# Motor_Driver.net
KiCad netlist of a schematic drawn in Altium Designer
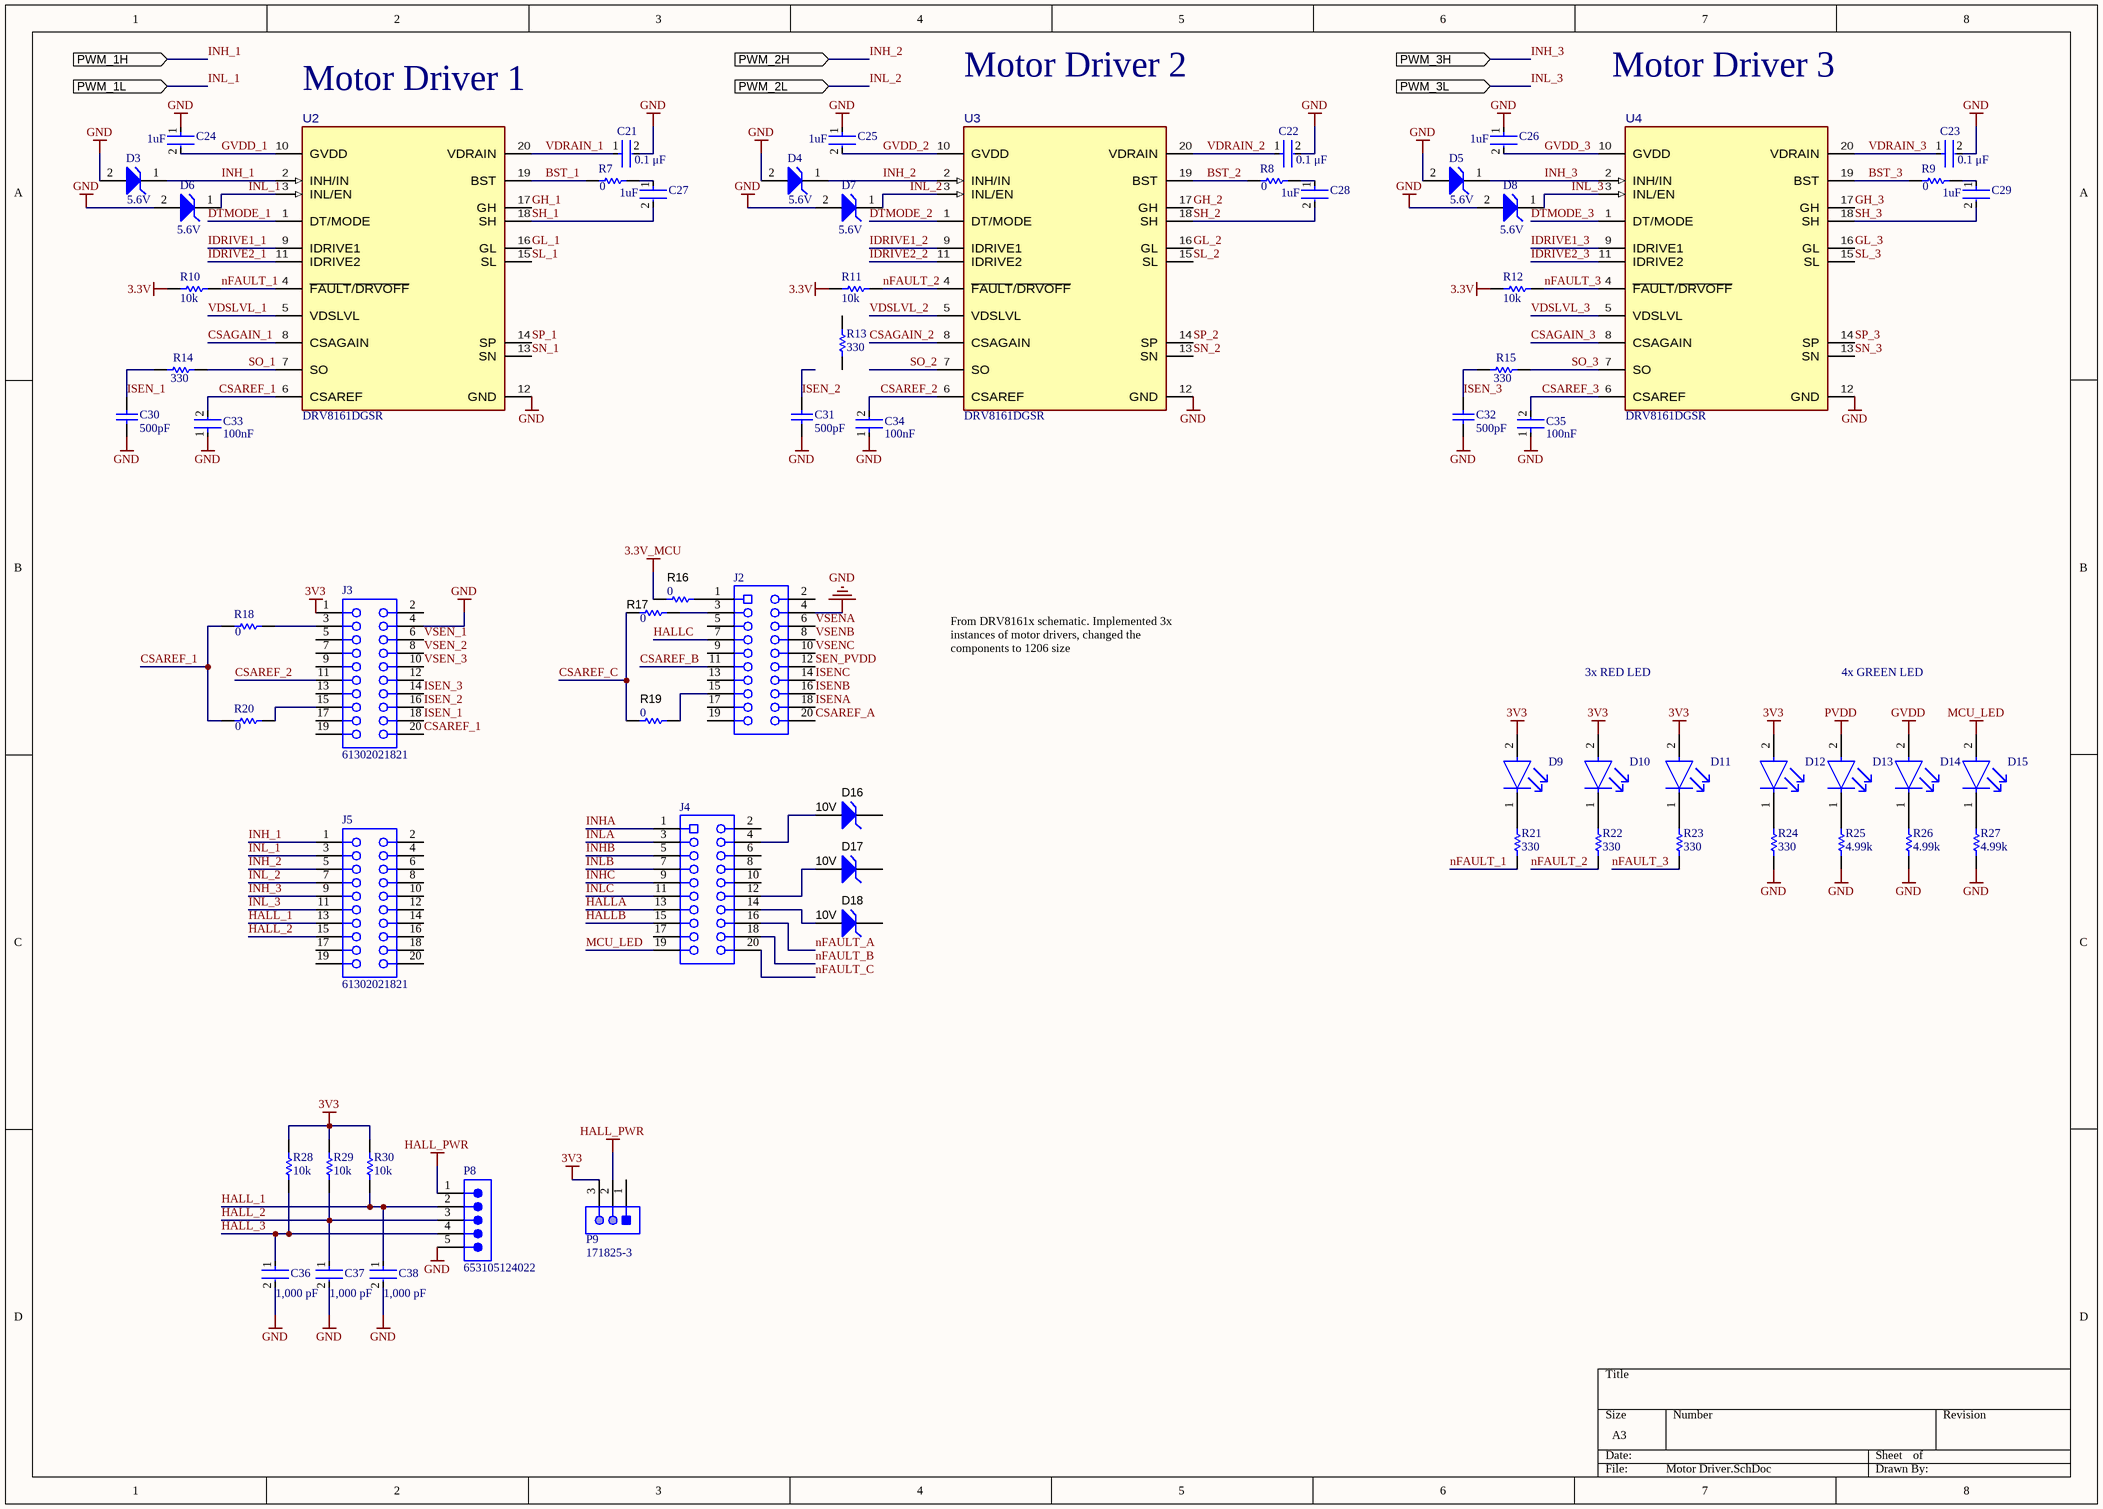
[diagram p0: Motor Driver.SchDoc]

(export (version "E")
  (design (tool "Eeschema 10.0.6"))
  (components
    (comp (ref "C21")
      (value "C1206C104K1RACTU")
      (footprint "FP-C1206C-EB-MFG")
      (description "CAP CER 0.1UF 100V X7R 1206")
      (fields
        (field (name "TOLERANCE") "0.1")
        (field (name "OCTOPART") "https://octopart.com/c1206c104k1ractu-kemet-89521")
        (field (name "CAPACITANCE") "0.1 μF")
      )
      (libsource (lib "Altium Content Vault") (part "b4654b650e69147ec39a6b967a45e02"))
    )
    (comp (ref "C22")
      (value "C1206C104K1RACTU")
      (footprint "FP-C1206C-EB-MFG")
      (description "CAP CER 0.1UF 100V X7R 1206")
      (fields
        (field (name "TOLERANCE") "0.1")
        (field (name "OCTOPART") "https://octopart.com/c1206c104k1ractu-kemet-89521")
        (field (name "CAPACITANCE") "0.1 μF")
      )
      (libsource (lib "Altium Content Vault") (part "b4654b650e69147ec39a6b967a45e02"))
    )
    (comp (ref "C23")
      (value "C1206C104K1RACTU")
      (footprint "FP-C1206C-EB-MFG")
      (description "CAP CER 0.1UF 100V X7R 1206")
      (fields
        (field (name "TOLERANCE") "0.1")
        (field (name "OCTOPART") "https://octopart.com/c1206c104k1ractu-kemet-89521")
        (field (name "CAPACITANCE") "0.1 μF")
      )
      (libsource (lib "Altium Content Vault") (part "b4654b650e69147ec39a6b967a45e02"))
    )
    (comp (ref "C24")
      (value "12063C105KAT2A")
      (footprint "FP-1206-L_3_2_0_2-W_1_6_0-IPC_A")
      (description "General Purpose Ceramic Capacitor, 1206, 1uF, 10%, X7R, 15%, 25V")
      (fields
        (field (name "CAPACITANCE") "1uF")
        (field (name "TOLERANCE") "10%")
        (field (name "VOLTAGE") "25V")
      )
      (libsource (lib "Altium Content Vault") (part "b4654b650e69147ec39a6b967a45e02"))
    )
    (comp (ref "C25")
      (value "12063C105KAT2A")
      (footprint "FP-1206-L_3_2_0_2-W_1_6_0-IPC_A")
      (description "General Purpose Ceramic Capacitor, 1206, 1uF, 10%, X7R, 15%, 25V")
      (fields
        (field (name "CAPACITANCE") "1uF")
        (field (name "TOLERANCE") "10%")
        (field (name "VOLTAGE") "25V")
      )
      (libsource (lib "Altium Content Vault") (part "b4654b650e69147ec39a6b967a45e02"))
    )
    (comp (ref "C26")
      (value "12063C105KAT2A")
      (footprint "FP-1206-L_3_2_0_2-W_1_6_0-IPC_A")
      (description "General Purpose Ceramic Capacitor, 1206, 1uF, 10%, X7R, 15%, 25V")
      (fields
        (field (name "CAPACITANCE") "1uF")
        (field (name "TOLERANCE") "10%")
        (field (name "VOLTAGE") "25V")
      )
      (libsource (lib "Altium Content Vault") (part "b4654b650e69147ec39a6b967a45e02"))
    )
    (comp (ref "C27")
      (value "12063C105KAT2A")
      (footprint "FP-1206-L_3_2_0_2-W_1_6_0-IPC_A")
      (description "General Purpose Ceramic Capacitor, 1206, 1uF, 10%, X7R, 15%, 25V")
      (fields
        (field (name "CAPACITANCE") "1uF")
        (field (name "TOLERANCE") "10%")
        (field (name "VOLTAGE") "25V")
      )
      (libsource (lib "Altium Content Vault") (part "b4654b650e69147ec39a6b967a45e02"))
    )
    (comp (ref "C28")
      (value "12063C105KAT2A")
      (footprint "FP-1206-L_3_2_0_2-W_1_6_0-IPC_A")
      (description "General Purpose Ceramic Capacitor, 1206, 1uF, 10%, X7R, 15%, 25V")
      (fields
        (field (name "CAPACITANCE") "1uF")
        (field (name "TOLERANCE") "10%")
        (field (name "VOLTAGE") "25V")
      )
      (libsource (lib "Altium Content Vault") (part "b4654b650e69147ec39a6b967a45e02"))
    )
    (comp (ref "C29")
      (value "12063C105KAT2A")
      (footprint "FP-1206-L_3_2_0_2-W_1_6_0-IPC_A")
      (description "General Purpose Ceramic Capacitor, 1206, 1uF, 10%, X7R, 15%, 25V")
      (fields
        (field (name "CAPACITANCE") "1uF")
        (field (name "TOLERANCE") "10%")
        (field (name "VOLTAGE") "25V")
      )
      (libsource (lib "Altium Content Vault") (part "b4654b650e69147ec39a6b967a45e02"))
    )
    (comp (ref "C30")
      (value "04025C501KAT2A")
      (footprint "CAPC1005X56X25NL10T15")
      (fields (field (name "MANUFACTURER") "AVX Interconnect / Elco") (field (name "PARAMETER 1") "500pF"))
      (libsource (lib "Altium Content Vault") (part "CAP"))
    )
    (comp (ref "C31")
      (value "04025C501KAT2A")
      (footprint "CAPC1005X56X25NL10T15")
      (fields (field (name "MANUFACTURER") "AVX Interconnect / Elco") (field (name "PARAMETER 1") "500pF"))
      (libsource (lib "Altium Content Vault") (part "CAP"))
    )
    (comp (ref "C32")
      (value "04025C501KAT2A")
      (footprint "CAPC1005X56X25NL10T15")
      (fields (field (name "MANUFACTURER") "AVX Interconnect / Elco") (field (name "PARAMETER 1") "500pF"))
      (libsource (lib "Altium Content Vault") (part "CAP"))
    )
    (comp (ref "C33")
      (value "12061C104KAZ2A")
      (footprint "FP-1206-L_3_2_0_2-W_1_6_0-MFG")
      (description "General Purpose Ceramic Capacitor, 1206, 100nF, 10%, X7R, 15%, 100V")
      (fields (field (name "TOLERANCE") "10%") (field (name "CAPACITANCE") "100nF"))
      (libsource (lib "Altium Content Vault") (part "b4654b650e69147ec39a6b967a45e02"))
    )
    (comp (ref "C34")
      (value "12061C104KAZ2A")
      (footprint "FP-1206-L_3_2_0_2-W_1_6_0-MFG")
      (description "General Purpose Ceramic Capacitor, 1206, 100nF, 10%, X7R, 15%, 100V")
      (fields (field (name "TOLERANCE") "10%") (field (name "CAPACITANCE") "100nF"))
      (libsource (lib "Altium Content Vault") (part "b4654b650e69147ec39a6b967a45e02"))
    )
    (comp (ref "C35")
      (value "12061C104KAZ2A")
      (footprint "FP-1206-L_3_2_0_2-W_1_6_0-MFG")
      (description "General Purpose Ceramic Capacitor, 1206, 100nF, 10%, X7R, 15%, 100V")
      (fields (field (name "TOLERANCE") "10%") (field (name "CAPACITANCE") "100nF"))
      (libsource (lib "Altium Content Vault") (part "b4654b650e69147ec39a6b967a45e02"))
    )
    (comp (ref "C36")
      (value "C1206C102J1GACTU")
      (footprint "FP-C1206C-EB-MFG")
      (fields
        (field (name "CAPACITANCE") "1,000 pF")
        (field (name "OCTOPART") "https://octopart.com/c1206c102j1gactu-kemet-99808")
        (field (name "TOLERANCE") "0.05")
        (field (name "MANUFACTURER") "KEMET")
      )
      (libsource (lib "Altium Content Vault") (part "b4654b650e69147ec39a6b967a45e02"))
    )
    (comp (ref "C37")
      (value "C1206C102J1GACTU")
      (footprint "FP-C1206C-EB-MFG")
      (fields
        (field (name "CAPACITANCE") "1,000 pF")
        (field (name "OCTOPART") "https://octopart.com/c1206c102j1gactu-kemet-99808")
        (field (name "TOLERANCE") "0.05")
        (field (name "MANUFACTURER") "KEMET")
      )
      (libsource (lib "Altium Content Vault") (part "b4654b650e69147ec39a6b967a45e02"))
    )
    (comp (ref "C38")
      (value "C1206C102J1GACTU")
      (footprint "FP-C1206C-EB-MFG")
      (fields
        (field (name "CAPACITANCE") "1,000 pF")
        (field (name "OCTOPART") "https://octopart.com/c1206c102j1gactu-kemet-99808")
        (field (name "TOLERANCE") "0.05")
        (field (name "MANUFACTURER") "KEMET")
      )
      (libsource (lib "Altium Content Vault") (part "b4654b650e69147ec39a6b967a45e02"))
    )
    (comp (ref "D3")
      (value "MMSZ5232BT1G")
      (footprint "ONSC-SOD-123-2-425-04_V")
      (description "Zener Voltage Regulator, 500 mW, 2-Pin SOD-123, Pb-Free, Tape and Reel")
      (fields (field (name "MANUFACTURER") "On Semiconductor") (field (name "VZ TYP (V)") "5.6V"))
      (libsource (lib "Altium Content Vault") (part "ONSC-K1A2-2"))
    )
    (comp (ref "D4")
      (value "MMSZ5232BT1G")
      (footprint "ONSC-SOD-123-2-425-04_V")
      (description "Zener Voltage Regulator, 500 mW, 2-Pin SOD-123, Pb-Free, Tape and Reel")
      (fields (field (name "MANUFACTURER") "On Semiconductor") (field (name "VZ TYP (V)") "5.6V"))
      (libsource (lib "Altium Content Vault") (part "ONSC-K1A2-2"))
    )
    (comp (ref "D5")
      (value "MMSZ5232BT1G")
      (footprint "ONSC-SOD-123-2-425-04_V")
      (description "Zener Voltage Regulator, 500 mW, 2-Pin SOD-123, Pb-Free, Tape and Reel")
      (fields (field (name "MANUFACTURER") "On Semiconductor") (field (name "VZ TYP (V)") "5.6V"))
      (libsource (lib "Altium Content Vault") (part "ONSC-K1A2-2"))
    )
    (comp (ref "D6")
      (value "MMSZ5232BT1G")
      (footprint "ONSC-SOD-123-2-425-04_V")
      (description "Zener Voltage Regulator, 500 mW, 2-Pin SOD-123, Pb-Free, Tape and Reel")
      (fields (field (name "MANUFACTURER") "On Semiconductor") (field (name "VZ TYP (V)") "5.6V"))
      (libsource (lib "Altium Content Vault") (part "ONSC-K1A2-2"))
    )
    (comp (ref "D7")
      (value "MMSZ5232BT1G")
      (footprint "ONSC-SOD-123-2-425-04_V")
      (description "Zener Voltage Regulator, 500 mW, 2-Pin SOD-123, Pb-Free, Tape and Reel")
      (fields (field (name "MANUFACTURER") "On Semiconductor") (field (name "VZ TYP (V)") "5.6V"))
      (libsource (lib "Altium Content Vault") (part "ONSC-K1A2-2"))
    )
    (comp (ref "D8")
      (value "MMSZ5232BT1G")
      (footprint "ONSC-SOD-123-2-425-04_V")
      (description "Zener Voltage Regulator, 500 mW, 2-Pin SOD-123, Pb-Free, Tape and Reel")
      (fields (field (name "MANUFACTURER") "On Semiconductor") (field (name "VZ TYP (V)") "5.6V"))
      (libsource (lib "Altium Content Vault") (part "ONSC-K1A2-2"))
    )
    (comp (ref "D9")
      (value "HSMS-C150")
      (footprint "FP-HSMS-C150-MFG")
      (description "LED RED DIFFUSED CHIP SMD")
      (libsource (lib "Altium Content Vault") (part "8706943c75ba83719d021d2fdc84c58"))
    )
    (comp (ref "D10")
      (value "HSMS-C150")
      (footprint "FP-HSMS-C150-MFG")
      (description "LED RED DIFFUSED CHIP SMD")
      (libsource (lib "Altium Content Vault") (part "8706943c75ba83719d021d2fdc84c58"))
    )
    (comp (ref "D11")
      (value "HSMS-C150")
      (footprint "FP-HSMS-C150-MFG")
      (description "LED RED DIFFUSED CHIP SMD")
      (libsource (lib "Altium Content Vault") (part "8706943c75ba83719d021d2fdc84c58"))
    )
    (comp (ref "D12")
      (value "LTST-C171GKT")
      (footprint "FP-LTST-C171GKT-MFG")
      (description "LED GREEN CLEAR CHIP SMD")
      (libsource (lib "Altium Content Vault") (part "8706943c75ba83719d021d2fdc84c58"))
    )
    (comp (ref "D13")
      (value "LTST-C171GKT")
      (footprint "FP-LTST-C171GKT-MFG")
      (description "LED GREEN CLEAR CHIP SMD")
      (libsource (lib "Altium Content Vault") (part "8706943c75ba83719d021d2fdc84c58"))
    )
    (comp (ref "D14")
      (value "LTST-C171GKT")
      (footprint "FP-LTST-C171GKT-MFG")
      (description "LED GREEN CLEAR CHIP SMD")
      (libsource (lib "Altium Content Vault") (part "8706943c75ba83719d021d2fdc84c58"))
    )
    (comp (ref "D15")
      (value "LTST-C171GKT")
      (footprint "FP-LTST-C171GKT-MFG")
      (description "LED GREEN CLEAR CHIP SMD")
      (libsource (lib "Altium Content Vault") (part "8706943c75ba83719d021d2fdc84c58"))
    )
    (comp (ref "D16")
      (value "10V")
      (footprint "SOD-123")
      (description "Diode, Zener, 10 V, 500 mW, SOD-123")
      (fields (field (name "MANUFACTURER") "Diodes Inc.") (field (name "PARTNUMBER") "DDZ10C-7"))
      (libsource (lib "Altium Vault - TI") (part "Zener"))
    )
    (comp (ref "D17")
      (value "10V")
      (footprint "SOD-123")
      (description "Diode, Zener, 10 V, 500 mW, SOD-123")
      (fields (field (name "MANUFACTURER") "Diodes Inc.") (field (name "PARTNUMBER") "DDZ10C-7"))
      (libsource (lib "Altium Vault - TI") (part "Zener"))
    )
    (comp (ref "D18")
      (value "10V")
      (footprint "SOD-123")
      (description "Diode, Zener, 10 V, 500 mW, SOD-123")
      (fields (field (name "MANUFACTURER") "Diodes Inc.") (field (name "PARTNUMBER") "DDZ10C-7"))
      (libsource (lib "Altium Vault - TI") (part "Zener"))
    )
    (comp (ref "J2")
      (value "SSQ-110-03-G-D")
      (footprint "Samtec_SSQ-110-03-x-D")
      (description "Receptacle, 2.54mm, 10x2, Gold, TH")
      (fields (field (name "MANUFACTURER") "Samtec") (field (name "PUBLISHER") "Texas Instruments"))
      (libsource (lib "Altium Vault - TI") (part "Receptacle_10x2"))
    )
    (comp (ref "J3")
      (value "61302021821")
      (footprint "61302021821")
      (libsource (lib "Altium Content Vault") (part "Header_Female_2R_20P"))
    )
    (comp (ref "J4")
      (value "SSQ-110-03-G-D")
      (footprint "Samtec_SSQ-110-03-x-D")
      (description "Receptacle, 2.54mm, 10x2, Gold, TH")
      (fields (field (name "MANUFACTURER") "Samtec") (field (name "PUBLISHER") "Texas Instruments"))
      (libsource (lib "Altium Vault - TI") (part "Receptacle_10x2"))
    )
    (comp (ref "J5")
      (value "61302021821")
      (footprint "61302021821")
      (libsource (lib "Altium Content Vault") (part "Header_Female_2R_20P"))
    )
    (comp (ref "P8")
      (value "653105124022")
      (footprint "653105124022")
      (libsource (lib "Altium Content Vault") (part "Header_Male_1R_05P"))
    )
    (comp (ref "P9")
      (value "171825-3")
      (footprint "TECO-171825-3_V")
      (fields (field (name "MANUFACTURER") "TE Connectivity"))
      (libsource (lib "Altium Content Vault") (part "CN-1P-M-R3"))
    )
    (comp (ref "R7")
      (value "ERJ-8GEY0R00V")
      (footprint "RESC3216X70X50NL05T20")
      (fields (field (name "MANUFACTURER") "Panasonic") (field (name "RESISTANCE") "0"))
      (libsource (lib "Altium Content Vault") (part "RES"))
    )
    (comp (ref "R8")
      (value "ERJ-8GEY0R00V")
      (footprint "RESC3216X70X50NL05T20")
      (fields (field (name "MANUFACTURER") "Panasonic") (field (name "RESISTANCE") "0"))
      (libsource (lib "Altium Content Vault") (part "RES"))
    )
    (comp (ref "R9")
      (value "ERJ-8GEY0R00V")
      (footprint "RESC3216X70X50NL05T20")
      (fields (field (name "MANUFACTURER") "Panasonic") (field (name "RESISTANCE") "0"))
      (libsource (lib "Altium Content Vault") (part "RES"))
    )
    (comp (ref "R10")
      (value "CRCW120610K0FKEAHP")
      (footprint "RESC3116X65X50NL20T20")
      (fields (field (name "MANUFACTURER") "Vishay Dale") (field (name "RESISTANCE") "10k"))
      (libsource (lib "Altium Content Vault") (part "RES"))
    )
    (comp (ref "R11")
      (value "CRCW120610K0FKEAHP")
      (footprint "RESC3116X65X50NL20T20")
      (fields (field (name "MANUFACTURER") "Vishay Dale") (field (name "RESISTANCE") "10k"))
      (libsource (lib "Altium Content Vault") (part "RES"))
    )
    (comp (ref "R12")
      (value "CRCW120610K0FKEAHP")
      (footprint "RESC3116X65X50NL20T20")
      (fields (field (name "MANUFACTURER") "Vishay Dale") (field (name "RESISTANCE") "10k"))
      (libsource (lib "Altium Content Vault") (part "RES"))
    )
    (comp (ref "R13")
      (value "ERJ-8GEYJ331V")
      (footprint "RESC3216X70X50NL05T20")
      (fields (field (name "MANUFACTURER") "Panasonic") (field (name "RESISTANCE") "330"))
      (libsource (lib "Altium Content Vault") (part "RES"))
    )
    (comp (ref "R14")
      (value "ERJ-8GEYJ331V")
      (footprint "RESC3216X70X50NL05T20")
      (fields (field (name "MANUFACTURER") "Panasonic") (field (name "RESISTANCE") "330"))
      (libsource (lib "Altium Content Vault") (part "RES"))
    )
    (comp (ref "R15")
      (value "ERJ-8GEYJ331V")
      (footprint "RESC3216X70X50NL05T20")
      (fields (field (name "MANUFACTURER") "Panasonic") (field (name "RESISTANCE") "330"))
      (libsource (lib "Altium Content Vault") (part "RES"))
    )
    (comp (ref "R16")
      (value "CRCW06030000Z0EA")
      (footprint "0603L")
      (description "RES, 0, 5%, 0.1 W, AEC-Q200 Grade 0, 0603")
      (fields (field (name "MANUFACTURER") "Vishay-Dale") (field (name "VALUEDISPLAYED") "0"))
      (libsource (lib "Altium Vault - TI") (part "Resistor"))
    )
    (comp (ref "R17")
      (value "CRCW06030000Z0EA")
      (footprint "0603L")
      (description "RES, 0, 5%, 0.1 W, AEC-Q200 Grade 0, 0603")
      (fields (field (name "MANUFACTURER") "Vishay-Dale") (field (name "VALUEDISPLAYED") "0"))
      (libsource (lib "Altium Vault - TI") (part "Resistor"))
    )
    (comp (ref "R18")
      (value "ERJ-8GEY0R00V")
      (footprint "RESC3216X70X50NL05T20")
      (fields (field (name "MANUFACTURER") "Panasonic") (field (name "RESISTANCE") "0"))
      (libsource (lib "Altium Content Vault") (part "RES"))
    )
    (comp (ref "R19")
      (value "CRCW06030000Z0EA")
      (footprint "0603L")
      (description "RES, 0, 5%, 0.1 W, AEC-Q200 Grade 0, 0603")
      (fields (field (name "MANUFACTURER") "Vishay-Dale") (field (name "VALUEDISPLAYED") "0"))
      (libsource (lib "Altium Vault - TI") (part "Resistor"))
    )
    (comp (ref "R20")
      (value "ERJ-8GEY0R00V")
      (footprint "RESC3216X70X50NL05T20")
      (fields (field (name "MANUFACTURER") "Panasonic") (field (name "RESISTANCE") "0"))
      (libsource (lib "Altium Content Vault") (part "RES"))
    )
    (comp (ref "R21")
      (value "ERJ-8GEYJ331V")
      (footprint "RESC3216X70X50NL05T20")
      (fields (field (name "MANUFACTURER") "Panasonic") (field (name "RESISTANCE") "330"))
      (libsource (lib "Altium Content Vault") (part "RES"))
    )
    (comp (ref "R22")
      (value "ERJ-8GEYJ331V")
      (footprint "RESC3216X70X50NL05T20")
      (fields (field (name "MANUFACTURER") "Panasonic") (field (name "RESISTANCE") "330"))
      (libsource (lib "Altium Content Vault") (part "RES"))
    )
    (comp (ref "R23")
      (value "ERJ-8GEYJ331V")
      (footprint "RESC3216X70X50NL05T20")
      (fields (field (name "MANUFACTURER") "Panasonic") (field (name "RESISTANCE") "330"))
      (libsource (lib "Altium Content Vault") (part "RES"))
    )
    (comp (ref "R24")
      (value "ERJ-8GEYJ331V")
      (footprint "RESC3216X70X50NL05T20")
      (fields (field (name "MANUFACTURER") "Panasonic") (field (name "RESISTANCE") "330"))
      (libsource (lib "Altium Content Vault") (part "RES"))
    )
    (comp (ref "R25")
      (value "CRCW12064K99FKEA")
      (footprint "RESC3216X60X45ML10T20")
      (fields (field (name "MANUFACTURER") "Vishay Dale") (field (name "RESISTANCE") "4.99k"))
      (libsource (lib "Altium Content Vault") (part "RES"))
    )
    (comp (ref "R26")
      (value "CRCW12064K99FKEA")
      (footprint "RESC3216X60X45ML10T20")
      (fields (field (name "MANUFACTURER") "Vishay Dale") (field (name "RESISTANCE") "4.99k"))
      (libsource (lib "Altium Content Vault") (part "RES"))
    )
    (comp (ref "R27")
      (value "CRCW12064K99FKEA")
      (footprint "RESC3216X60X45ML10T20")
      (fields (field (name "MANUFACTURER") "Vishay Dale") (field (name "RESISTANCE") "4.99k"))
      (libsource (lib "Altium Content Vault") (part "RES"))
    )
    (comp (ref "R28")
      (value "CRCW120610K0FKEAHP")
      (footprint "RESC3116X65X50NL20T20")
      (fields (field (name "MANUFACTURER") "Vishay Dale") (field (name "RESISTANCE") "10k"))
      (libsource (lib "Altium Content Vault") (part "RES"))
    )
    (comp (ref "R29")
      (value "CRCW120610K0FKEAHP")
      (footprint "RESC3116X65X50NL20T20")
      (fields (field (name "MANUFACTURER") "Vishay Dale") (field (name "RESISTANCE") "10k"))
      (libsource (lib "Altium Content Vault") (part "RES"))
    )
    (comp (ref "R30")
      (value "CRCW120610K0FKEAHP")
      (footprint "RESC3116X65X50NL20T20")
      (fields (field (name "MANUFACTURER") "Vishay Dale") (field (name "RESISTANCE") "10k"))
      (libsource (lib "Altium Content Vault") (part "RES"))
    )
    (comp (ref "U2")
      (value "DRV8161DGSR")
      (footprint "DGS0020A-MFG")
      (description "100-V Half-Bridge Smart Gate Driver")
      (fields (field (name "MANUFACTURER") "Texas Instruments") (field (name "PARTNUMBER") "DRV8161DGSR"))
      (libsource (lib "Altium Vault - TI") (part "SYM-DRV8161DGSR"))
    )
    (comp (ref "U3")
      (value "DRV8161DGSR")
      (footprint "DGS0020A-MFG")
      (description "100-V Half-Bridge Smart Gate Driver")
      (fields (field (name "MANUFACTURER") "Texas Instruments") (field (name "PARTNUMBER") "DRV8161DGSR"))
      (libsource (lib "Altium Vault - TI") (part "SYM-DRV8161DGSR"))
    )
    (comp (ref "U4")
      (value "DRV8161DGSR")
      (footprint "DGS0020A-MFG")
      (description "100-V Half-Bridge Smart Gate Driver")
      (fields (field (name "MANUFACTURER") "Texas Instruments") (field (name "PARTNUMBER") "DRV8161DGSR"))
      (libsource (lib "Altium Vault - TI") (part "SYM-DRV8161DGSR"))
    )
  )
  (nets
    (net (code "1") (name "/BST_1") (class "Default")
      (node (ref "R7") (pin "1") (pinfunction "1_1") (pintype "passive"))
      (node (ref "U2") (pin "19") (pinfunction "BST_19") (pintype "passive"))
    )
    (net (code "2") (name "/BST_2") (class "Default")
      (node (ref "R8") (pin "1") (pinfunction "1_1") (pintype "passive"))
      (node (ref "U3") (pin "19") (pinfunction "BST_19") (pintype "passive"))
    )
    (net (code "3") (name "/BST_3") (class "Default")
      (node (ref "R9") (pin "1") (pinfunction "1_1") (pintype "passive"))
      (node (ref "U4") (pin "19") (pinfunction "BST_19") (pintype "passive"))
    )
    (net (code "4") (name "/CSAGAIN_1") (class "Default")
      (node (ref "U2") (pin "8") (pinfunction "CSAGAIN_8") (pintype "passive"))
    )
    (net (code "5") (name "/CSAGAIN_2") (class "Default")
      (node (ref "U3") (pin "8") (pinfunction "CSAGAIN_8") (pintype "passive"))
    )
    (net (code "6") (name "/CSAGAIN_3") (class "Default")
      (node (ref "U4") (pin "8") (pinfunction "CSAGAIN_8") (pintype "passive"))
    )
    (net (code "7") (name "/CSAREF_1") (class "Default")
      (node (ref "C33") (pin "2") (pinfunction "2_2") (pintype "passive"))
      (node (ref "J3") (pin "20") (pinfunction "20_20") (pintype "passive"))
      (node (ref "R18") (pin "1") (pinfunction "1_1") (pintype "passive"))
      (node (ref "R20") (pin "1") (pinfunction "1_1") (pintype "passive"))
      (node (ref "U2") (pin "6") (pinfunction "CSAREF_6") (pintype "passive"))
    )
    (net (code "8") (name "/CSAREF_2") (class "Default")
      (node (ref "C34") (pin "2") (pinfunction "2_2") (pintype "passive"))
      (node (ref "J3") (pin "11") (pinfunction "11_11") (pintype "passive"))
      (node (ref "U3") (pin "6") (pinfunction "CSAREF_6") (pintype "passive"))
    )
    (net (code "9") (name "/CSAREF_3") (class "Default")
      (node (ref "C35") (pin "2") (pinfunction "2_2") (pintype "passive"))
      (node (ref "U4") (pin "6") (pinfunction "CSAREF_6") (pintype "passive"))
    )
    (net (code "10") (name "/CSAREF_A") (class "Default")
      (node (ref "J2") (pin "20") (pinfunction "20_20") (pintype "passive"))
    )
    (net (code "11") (name "/CSAREF_B") (class "Default")
      (node (ref "J2") (pin "11") (pinfunction "11_11") (pintype "passive"))
    )
    (net (code "12") (name "/CSAREF_C") (class "Default")
      (node (ref "R17") (pin "1") (pinfunction "1_1") (pintype "passive"))
      (node (ref "R19") (pin "1") (pinfunction "1_1") (pintype "passive"))
    )
    (net (code "13") (name "/DTMODE_1") (class "Default")
      (node (ref "U2") (pin "1") (pinfunction "DT/MODE_1") (pintype "passive"))
    )
    (net (code "14") (name "/DTMODE_2") (class "Default")
      (node (ref "U3") (pin "1") (pinfunction "DT/MODE_1") (pintype "passive"))
    )
    (net (code "15") (name "/DTMODE_3") (class "Default")
      (node (ref "U4") (pin "1") (pinfunction "DT/MODE_1") (pintype "passive"))
    )
    (net (code "16") (name "/GH_1") (class "Default")
      (node (ref "U2") (pin "17") (pinfunction "GH_17") (pintype "passive"))
    )
    (net (code "17") (name "/GH_2") (class "Default")
      (node (ref "U3") (pin "17") (pinfunction "GH_17") (pintype "passive"))
    )
    (net (code "18") (name "/GH_3") (class "Default")
      (node (ref "U4") (pin "17") (pinfunction "GH_17") (pintype "passive"))
    )
    (net (code "19") (name "/GL_1") (class "Default")
      (node (ref "U2") (pin "16") (pinfunction "GL_16") (pintype "passive"))
    )
    (net (code "20") (name "/GL_2") (class "Default")
      (node (ref "U3") (pin "16") (pinfunction "GL_16") (pintype "passive"))
    )
    (net (code "21") (name "/GL_3") (class "Default")
      (node (ref "U4") (pin "16") (pinfunction "GL_16") (pintype "passive"))
    )
    (net (code "22") (name "/GVDD_1") (class "Default")
      (node (ref "C24") (pin "2") (pinfunction "2_2") (pintype "passive"))
      (node (ref "U2") (pin "10") (pinfunction "GVDD_10") (pintype "power_in"))
    )
    (net (code "23") (name "/GVDD_2") (class "Default")
      (node (ref "C25") (pin "2") (pinfunction "2_2") (pintype "passive"))
      (node (ref "U3") (pin "10") (pinfunction "GVDD_10") (pintype "power_in"))
    )
    (net (code "24") (name "/GVDD_3") (class "Default")
      (node (ref "C26") (pin "2") (pinfunction "2_2") (pintype "passive"))
      (node (ref "U4") (pin "10") (pinfunction "GVDD_10") (pintype "power_in"))
    )
    (net (code "25") (name "/HALLA") (class "Default")
      (node (ref "J4") (pin "13") (pinfunction "13_13") (pintype "passive"))
    )
    (net (code "26") (name "/HALLB") (class "Default")
      (node (ref "J4") (pin "15") (pinfunction "15_15") (pintype "passive"))
    )
    (net (code "27") (name "/HALLC") (class "Default")
      (node (ref "J2") (pin "7") (pinfunction "7_7") (pintype "passive"))
    )
    (net (code "28") (name "/HALL_1") (class "Default")
      (node (ref "C38") (pin "1") (pinfunction "1_1") (pintype "passive"))
      (node (ref "J5") (pin "13") (pinfunction "13_13") (pintype "passive"))
      (node (ref "P8") (pin "2") (pinfunction "2_2") (pintype "passive"))
      (node (ref "R30") (pin "1") (pinfunction "1_1") (pintype "passive"))
    )
    (net (code "29") (name "/HALL_2") (class "Default")
      (node (ref "C37") (pin "1") (pinfunction "1_1") (pintype "passive"))
      (node (ref "J5") (pin "15") (pinfunction "15_15") (pintype "passive"))
      (node (ref "P8") (pin "3") (pinfunction "3_3") (pintype "passive"))
      (node (ref "R29") (pin "1") (pinfunction "1_1") (pintype "passive"))
    )
    (net (code "30") (name "/HALL_3") (class "Default")
      (node (ref "C36") (pin "1") (pinfunction "1_1") (pintype "passive"))
      (node (ref "P8") (pin "4") (pinfunction "4_4") (pintype "passive"))
      (node (ref "R28") (pin "1") (pinfunction "1_1") (pintype "passive"))
    )
    (net (code "31") (name "/IDRIVE1_1") (class "Default")
      (node (ref "U2") (pin "9") (pinfunction "IDRIVE1_9") (pintype "passive"))
    )
    (net (code "32") (name "/IDRIVE1_2") (class "Default")
      (node (ref "U3") (pin "9") (pinfunction "IDRIVE1_9") (pintype "passive"))
    )
    (net (code "33") (name "/IDRIVE1_3") (class "Default")
      (node (ref "U4") (pin "9") (pinfunction "IDRIVE1_9") (pintype "passive"))
    )
    (net (code "34") (name "/IDRIVE2_1") (class "Default")
      (node (ref "U2") (pin "11") (pinfunction "IDRIVE2_11") (pintype "passive"))
    )
    (net (code "35") (name "/IDRIVE2_2") (class "Default")
      (node (ref "U3") (pin "11") (pinfunction "IDRIVE2_11") (pintype "passive"))
    )
    (net (code "36") (name "/IDRIVE2_3") (class "Default")
      (node (ref "U4") (pin "11") (pinfunction "IDRIVE2_11") (pintype "passive"))
    )
    (net (code "37") (name "/INHA") (class "Default")
      (node (ref "J4") (pin "1") (pinfunction "1_1") (pintype "passive"))
    )
    (net (code "38") (name "/INHB") (class "Default")
      (node (ref "J4") (pin "5") (pinfunction "5_5") (pintype "passive"))
    )
    (net (code "39") (name "/INHC") (class "Default")
      (node (ref "J4") (pin "9") (pinfunction "9_9") (pintype "passive"))
    )
    (net (code "40") (name "/INH_1") (class "Default")
      (node (ref "D3") (pin "1") (pinfunction "K_1") (pintype "passive"))
      (node (ref "J5") (pin "1") (pinfunction "1_1") (pintype "passive"))
      (node (ref "U2") (pin "2") (pinfunction "INH/IN_2") (pintype "input"))
    )
    (net (code "41") (name "/INH_2") (class "Default")
      (node (ref "D4") (pin "1") (pinfunction "K_1") (pintype "passive"))
      (node (ref "J5") (pin "5") (pinfunction "5_5") (pintype "passive"))
      (node (ref "U3") (pin "2") (pinfunction "INH/IN_2") (pintype "input"))
    )
    (net (code "42") (name "/INH_3") (class "Default")
      (node (ref "D5") (pin "1") (pinfunction "K_1") (pintype "passive"))
      (node (ref "J5") (pin "9") (pinfunction "9_9") (pintype "passive"))
      (node (ref "U4") (pin "2") (pinfunction "INH/IN_2") (pintype "input"))
    )
    (net (code "43") (name "/INLA") (class "Default")
      (node (ref "J4") (pin "3") (pinfunction "3_3") (pintype "passive"))
    )
    (net (code "44") (name "/INLB") (class "Default")
      (node (ref "J4") (pin "7") (pinfunction "7_7") (pintype "passive"))
    )
    (net (code "45") (name "/INLC") (class "Default")
      (node (ref "J4") (pin "11") (pinfunction "11_11") (pintype "passive"))
    )
    (net (code "46") (name "/INL_1") (class "Default")
      (node (ref "D6") (pin "1") (pinfunction "K_1") (pintype "passive"))
      (node (ref "J5") (pin "3") (pinfunction "3_3") (pintype "passive"))
      (node (ref "U2") (pin "3") (pinfunction "INL/EN_3") (pintype "input"))
    )
    (net (code "47") (name "/INL_2") (class "Default")
      (node (ref "D7") (pin "1") (pinfunction "K_1") (pintype "passive"))
      (node (ref "J5") (pin "7") (pinfunction "7_7") (pintype "passive"))
      (node (ref "U3") (pin "3") (pinfunction "INL/EN_3") (pintype "input"))
    )
    (net (code "48") (name "/INL_3") (class "Default")
      (node (ref "D8") (pin "1") (pinfunction "K_1") (pintype "passive"))
      (node (ref "J5") (pin "11") (pinfunction "11_11") (pintype "passive"))
      (node (ref "U4") (pin "3") (pinfunction "INL/EN_3") (pintype "input"))
    )
    (net (code "49") (name "/ISENA") (class "Default")
      (node (ref "J2") (pin "18") (pinfunction "18_18") (pintype "passive"))
    )
    (net (code "50") (name "/ISENB") (class "Default")
      (node (ref "J2") (pin "16") (pinfunction "16_16") (pintype "passive"))
    )
    (net (code "51") (name "/ISENC") (class "Default")
      (node (ref "J2") (pin "14") (pinfunction "14_14") (pintype "passive"))
    )
    (net (code "52") (name "/ISEN_1") (class "Default")
      (node (ref "C30") (pin "2") (pinfunction "2_2") (pintype "passive"))
      (node (ref "J3") (pin "18") (pinfunction "18_18") (pintype "passive"))
      (node (ref "R14") (pin "1") (pinfunction "1_1") (pintype "passive"))
    )
    (net (code "53") (name "/ISEN_2") (class "Default")
      (node (ref "C31") (pin "2") (pinfunction "2_2") (pintype "passive"))
      (node (ref "J3") (pin "16") (pinfunction "16_16") (pintype "passive"))
    )
    (net (code "54") (name "/ISEN_3") (class "Default")
      (node (ref "C32") (pin "2") (pinfunction "2_2") (pintype "passive"))
      (node (ref "J3") (pin "14") (pinfunction "14_14") (pintype "passive"))
      (node (ref "R15") (pin "1") (pinfunction "1_1") (pintype "passive"))
    )
    (net (code "55") (name "/SEN_PVDD") (class "Default")
      (node (ref "J2") (pin "12") (pinfunction "12_12") (pintype "passive"))
    )
    (net (code "56") (name "/SH_1") (class "Default")
      (node (ref "C27") (pin "2") (pinfunction "2_2") (pintype "passive"))
      (node (ref "U2") (pin "18") (pinfunction "SH_18") (pintype "passive"))
    )
    (net (code "57") (name "/SH_2") (class "Default")
      (node (ref "C28") (pin "2") (pinfunction "2_2") (pintype "passive"))
      (node (ref "U3") (pin "18") (pinfunction "SH_18") (pintype "passive"))
    )
    (net (code "58") (name "/SH_3") (class "Default")
      (node (ref "C29") (pin "2") (pinfunction "2_2") (pintype "passive"))
      (node (ref "U4") (pin "18") (pinfunction "SH_18") (pintype "passive"))
    )
    (net (code "59") (name "/SL_1") (class "Default")
      (node (ref "U2") (pin "15") (pinfunction "SL_15") (pintype "passive"))
    )
    (net (code "60") (name "/SL_2") (class "Default")
      (node (ref "U3") (pin "15") (pinfunction "SL_15") (pintype "passive"))
    )
    (net (code "61") (name "/SL_3") (class "Default")
      (node (ref "U4") (pin "15") (pinfunction "SL_15") (pintype "passive"))
    )
    (net (code "62") (name "/SN_1") (class "Default")
      (node (ref "U2") (pin "13") (pinfunction "SN_13") (pintype "passive"))
    )
    (net (code "63") (name "/SN_2") (class "Default")
      (node (ref "U3") (pin "13") (pinfunction "SN_13") (pintype "passive"))
    )
    (net (code "64") (name "/SN_3") (class "Default")
      (node (ref "U4") (pin "13") (pinfunction "SN_13") (pintype "passive"))
    )
    (net (code "65") (name "/SO_1") (class "Default")
      (node (ref "R14") (pin "2") (pinfunction "2_2") (pintype "passive"))
      (node (ref "U2") (pin "7") (pinfunction "SO_7") (pintype "passive"))
    )
    (net (code "66") (name "/SO_2") (class "Default")
      (node (ref "U3") (pin "7") (pinfunction "SO_7") (pintype "passive"))
    )
    (net (code "67") (name "/SO_3") (class "Default")
      (node (ref "R15") (pin "2") (pinfunction "2_2") (pintype "passive"))
      (node (ref "U4") (pin "7") (pinfunction "SO_7") (pintype "passive"))
    )
    (net (code "68") (name "/SP_1") (class "Default")
      (node (ref "U2") (pin "14") (pinfunction "SP_14") (pintype "passive"))
    )
    (net (code "69") (name "/SP_2") (class "Default")
      (node (ref "U3") (pin "14") (pinfunction "SP_14") (pintype "passive"))
    )
    (net (code "70") (name "/SP_3") (class "Default")
      (node (ref "U4") (pin "14") (pinfunction "SP_14") (pintype "passive"))
    )
    (net (code "71") (name "/VDRAIN_1") (class "Default")
      (node (ref "C21") (pin "1") (pinfunction "1_1") (pintype "passive"))
      (node (ref "U2") (pin "20") (pinfunction "VDRAIN_20") (pintype "power_in"))
    )
    (net (code "72") (name "/VDRAIN_2") (class "Default")
      (node (ref "C22") (pin "1") (pinfunction "1_1") (pintype "passive"))
      (node (ref "U3") (pin "20") (pinfunction "VDRAIN_20") (pintype "power_in"))
    )
    (net (code "73") (name "/VDRAIN_3") (class "Default")
      (node (ref "C23") (pin "1") (pinfunction "1_1") (pintype "passive"))
      (node (ref "U4") (pin "20") (pinfunction "VDRAIN_20") (pintype "power_in"))
    )
    (net (code "74") (name "/VDSLVL_1") (class "Default")
      (node (ref "U2") (pin "5") (pinfunction "VDSLVL_5") (pintype "passive"))
    )
    (net (code "75") (name "/VDSLVL_2") (class "Default")
      (node (ref "U3") (pin "5") (pinfunction "VDSLVL_5") (pintype "passive"))
    )
    (net (code "76") (name "/VDSLVL_3") (class "Default")
      (node (ref "U4") (pin "5") (pinfunction "VDSLVL_5") (pintype "passive"))
    )
    (net (code "77") (name "/VSENA") (class "Default")
      (node (ref "J2") (pin "6") (pinfunction "6_6") (pintype "passive"))
    )
    (net (code "78") (name "/VSENB") (class "Default")
      (node (ref "J2") (pin "8") (pinfunction "8_8") (pintype "passive"))
    )
    (net (code "79") (name "/VSENC") (class "Default")
      (node (ref "J2") (pin "10") (pinfunction "10_10") (pintype "passive"))
    )
    (net (code "80") (name "/VSEN_1") (class "Default")
      (node (ref "J3") (pin "6") (pinfunction "6_6") (pintype "passive"))
    )
    (net (code "81") (name "/VSEN_2") (class "Default")
      (node (ref "J3") (pin "8") (pinfunction "8_8") (pintype "passive"))
    )
    (net (code "82") (name "/VSEN_3") (class "Default")
      (node (ref "J3") (pin "10") (pinfunction "10_10") (pintype "passive"))
    )
    (net (code "83") (name "/nFAULT_1") (class "Default")
      (node (ref "R10") (pin "2") (pinfunction "2_2") (pintype "passive"))
      (node (ref "R21") (pin "1") (pinfunction "1_1") (pintype "passive"))
      (node (ref "U2") (pin "4") (pinfunction "~{FAULT}/~{DRVOFF}_4") (pintype "passive"))
    )
    (net (code "84") (name "/nFAULT_2") (class "Default")
      (node (ref "R11") (pin "2") (pinfunction "2_2") (pintype "passive"))
      (node (ref "R22") (pin "1") (pinfunction "1_1") (pintype "passive"))
      (node (ref "U3") (pin "4") (pinfunction "~{FAULT}/~{DRVOFF}_4") (pintype "passive"))
    )
    (net (code "85") (name "/nFAULT_3") (class "Default")
      (node (ref "R12") (pin "2") (pinfunction "2_2") (pintype "passive"))
      (node (ref "R23") (pin "1") (pinfunction "1_1") (pintype "passive"))
      (node (ref "U4") (pin "4") (pinfunction "~{FAULT}/~{DRVOFF}_4") (pintype "passive"))
    )
    (net (code "86") (name "/nFAULT_A") (class "Default")
      (node (ref "J4") (pin "16") (pinfunction "16_16") (pintype "passive"))
    )
    (net (code "87") (name "/nFAULT_B") (class "Default")
      (node (ref "J4") (pin "18") (pinfunction "18_18") (pintype "passive"))
    )
    (net (code "88") (name "/nFAULT_C") (class "Default")
      (node (ref "J4") (pin "20") (pinfunction "20_20") (pintype "passive"))
    )
    (net (code "89") (name "3.3V") (class "Default")
      (node (ref "R10") (pin "1") (pinfunction "1_1") (pintype "passive"))
      (node (ref "R11") (pin "1") (pinfunction "1_1") (pintype "passive"))
      (node (ref "R12") (pin "1") (pinfunction "1_1") (pintype "passive"))
    )
    (net (code "90") (name "3.3V_MCU") (class "Default")
      (node (ref "R16") (pin "1") (pinfunction "1_1") (pintype "passive"))
    )
    (net (code "91") (name "3V3") (class "Default")
      (node (ref "D10") (pin "2") (pinfunction "A_2") (pintype "passive"))
      (node (ref "D11") (pin "2") (pinfunction "A_2") (pintype "passive"))
      (node (ref "D12") (pin "2") (pinfunction "A_2") (pintype "passive"))
      (node (ref "D9") (pin "2") (pinfunction "A_2") (pintype "passive"))
      (node (ref "J3") (pin "1") (pinfunction "1_1") (pintype "passive"))
      (node (ref "P9") (pin "3") (pinfunction "3_3") (pintype "passive"))
      (node (ref "R28") (pin "2") (pinfunction "2_2") (pintype "passive"))
      (node (ref "R29") (pin "2") (pinfunction "2_2") (pintype "passive"))
      (node (ref "R30") (pin "2") (pinfunction "2_2") (pintype "passive"))
    )
    (net (code "92") (name "GND") (class "Default")
      (node (ref "C21") (pin "2") (pinfunction "2_2") (pintype "passive"))
      (node (ref "C22") (pin "2") (pinfunction "2_2") (pintype "passive"))
      (node (ref "C23") (pin "2") (pinfunction "2_2") (pintype "passive"))
      (node (ref "C24") (pin "1") (pinfunction "1_1") (pintype "passive"))
      (node (ref "C25") (pin "1") (pinfunction "1_1") (pintype "passive"))
      (node (ref "C26") (pin "1") (pinfunction "1_1") (pintype "passive"))
      (node (ref "C30") (pin "1") (pinfunction "1_1") (pintype "passive"))
      (node (ref "C31") (pin "1") (pinfunction "1_1") (pintype "passive"))
      (node (ref "C32") (pin "1") (pinfunction "1_1") (pintype "passive"))
      (node (ref "C33") (pin "1") (pinfunction "1_1") (pintype "passive"))
      (node (ref "C34") (pin "1") (pinfunction "1_1") (pintype "passive"))
      (node (ref "C35") (pin "1") (pinfunction "1_1") (pintype "passive"))
      (node (ref "C36") (pin "2") (pinfunction "2_2") (pintype "passive"))
      (node (ref "C37") (pin "2") (pinfunction "2_2") (pintype "passive"))
      (node (ref "C38") (pin "2") (pinfunction "2_2") (pintype "passive"))
      (node (ref "D3") (pin "2") (pinfunction "A_2") (pintype "passive"))
      (node (ref "D4") (pin "2") (pinfunction "A_2") (pintype "passive"))
      (node (ref "D5") (pin "2") (pinfunction "A_2") (pintype "passive"))
      (node (ref "D6") (pin "2") (pinfunction "A_2") (pintype "passive"))
      (node (ref "D7") (pin "2") (pinfunction "A_2") (pintype "passive"))
      (node (ref "D8") (pin "2") (pinfunction "A_2") (pintype "passive"))
      (node (ref "J2") (pin "4") (pinfunction "4_4") (pintype "passive"))
      (node (ref "J3") (pin "4") (pinfunction "4_4") (pintype "passive"))
      (node (ref "P8") (pin "5") (pinfunction "5_5") (pintype "passive"))
      (node (ref "R24") (pin "1") (pinfunction "1_1") (pintype "passive"))
      (node (ref "R25") (pin "1") (pinfunction "1_1") (pintype "passive"))
      (node (ref "R26") (pin "1") (pinfunction "1_1") (pintype "passive"))
      (node (ref "R27") (pin "1") (pinfunction "1_1") (pintype "passive"))
      (node (ref "U2") (pin "12") (pinfunction "GND_12") (pintype "power_in"))
      (node (ref "U3") (pin "12") (pinfunction "GND_12") (pintype "power_in"))
      (node (ref "U4") (pin "12") (pinfunction "GND_12") (pintype "power_in"))
    )
    (net (code "93") (name "GVDD") (class "Default")
      (node (ref "D14") (pin "2") (pinfunction "A_2") (pintype "passive"))
    )
    (net (code "94") (name "HALL_PWR") (class "Default")
      (node (ref "P8") (pin "1") (pinfunction "1_1") (pintype "passive"))
      (node (ref "P9") (pin "2") (pinfunction "2_2") (pintype "passive"))
    )
    (net (code "95") (name "MCU_LED") (class "Default")
      (node (ref "D15") (pin "2") (pinfunction "A_2") (pintype "passive"))
      (node (ref "J4") (pin "19") (pinfunction "19_19") (pintype "passive"))
    )
    (net (code "96") (name "Net-(C27-Pad1)") (class "Default")
      (node (ref "C27") (pin "1") (pinfunction "1_1") (pintype "passive"))
      (node (ref "R7") (pin "2") (pinfunction "2_2") (pintype "passive"))
    )
    (net (code "97") (name "Net-(C28-Pad1)") (class "Default")
      (node (ref "C28") (pin "1") (pinfunction "1_1") (pintype "passive"))
      (node (ref "R8") (pin "2") (pinfunction "2_2") (pintype "passive"))
    )
    (net (code "98") (name "Net-(C29-Pad1)") (class "Default")
      (node (ref "C29") (pin "1") (pinfunction "1_1") (pintype "passive"))
      (node (ref "R9") (pin "2") (pinfunction "2_2") (pintype "passive"))
    )
    (net (code "99") (name "Net-(D9-C)") (class "Default")
      (node (ref "D9") (pin "1") (pinfunction "C_1") (pintype "passive"))
      (node (ref "R21") (pin "2") (pinfunction "2_2") (pintype "passive"))
    )
    (net (code "100") (name "Net-(D10-C)") (class "Default")
      (node (ref "D10") (pin "1") (pinfunction "C_1") (pintype "passive"))
      (node (ref "R22") (pin "2") (pinfunction "2_2") (pintype "passive"))
    )
    (net (code "101") (name "Net-(D11-C)") (class "Default")
      (node (ref "D11") (pin "1") (pinfunction "C_1") (pintype "passive"))
      (node (ref "R23") (pin "2") (pinfunction "2_2") (pintype "passive"))
    )
    (net (code "102") (name "Net-(D12-C)") (class "Default")
      (node (ref "D12") (pin "1") (pinfunction "C_1") (pintype "passive"))
      (node (ref "R24") (pin "2") (pinfunction "2_2") (pintype "passive"))
    )
    (net (code "103") (name "Net-(D13-C)") (class "Default")
      (node (ref "D13") (pin "1") (pinfunction "C_1") (pintype "passive"))
      (node (ref "R25") (pin "2") (pinfunction "2_2") (pintype "passive"))
    )
    (net (code "104") (name "Net-(D14-C)") (class "Default")
      (node (ref "D14") (pin "1") (pinfunction "C_1") (pintype "passive"))
      (node (ref "R26") (pin "2") (pinfunction "2_2") (pintype "passive"))
    )
    (net (code "105") (name "Net-(D15-C)") (class "Default")
      (node (ref "D15") (pin "1") (pinfunction "C_1") (pintype "passive"))
      (node (ref "R27") (pin "2") (pinfunction "2_2") (pintype "passive"))
    )
    (net (code "106") (name "Net-(D16-A)") (class "Default")
      (node (ref "D16") (pin "2") (pinfunction "A_2") (pintype "passive"))
      (node (ref "J4") (pin "4") (pinfunction "4_4") (pintype "passive"))
    )
    (net (code "107") (name "Net-(D17-A)") (class "Default")
      (node (ref "D17") (pin "2") (pinfunction "A_2") (pintype "passive"))
      (node (ref "J4") (pin "12") (pinfunction "12_12") (pintype "passive"))
    )
    (net (code "108") (name "Net-(D18-A)") (class "Default")
      (node (ref "D18") (pin "2") (pinfunction "A_2") (pintype "passive"))
      (node (ref "J4") (pin "14") (pinfunction "14_14") (pintype "passive"))
    )
    (net (code "109") (name "Net-(J2-Pad1)") (class "Default")
      (node (ref "J2") (pin "1") (pinfunction "1_1") (pintype "passive"))
      (node (ref "R16") (pin "2") (pinfunction "2_2") (pintype "passive"))
    )
    (net (code "110") (name "Net-(J2-Pad3)") (class "Default")
      (node (ref "J2") (pin "3") (pinfunction "3_3") (pintype "passive"))
      (node (ref "R17") (pin "2") (pinfunction "2_2") (pintype "passive"))
    )
    (net (code "111") (name "Net-(J2-Pad15)") (class "Default")
      (node (ref "J2") (pin "15") (pinfunction "15_15") (pintype "passive"))
      (node (ref "R19") (pin "2") (pinfunction "2_2") (pintype "passive"))
    )
    (net (code "112") (name "Net-(J3-Pad3)") (class "Default")
      (node (ref "J3") (pin "3") (pinfunction "3_3") (pintype "passive"))
      (node (ref "R18") (pin "2") (pinfunction "2_2") (pintype "passive"))
    )
    (net (code "113") (name "Net-(J3-Pad15)") (class "Default")
      (node (ref "J3") (pin "15") (pinfunction "15_15") (pintype "passive"))
      (node (ref "R20") (pin "2") (pinfunction "2_2") (pintype "passive"))
    )
    (net (code "114") (name "PVDD") (class "Default")
      (node (ref "D13") (pin "2") (pinfunction "A_2") (pintype "passive"))
    )
    (net (code "115") (name "unconnected-(D16-K-Pad1)") (class "Default")
      (node (ref "D16") (pin "1") (pinfunction "K_1") (pintype "passive"))
    )
    (net (code "116") (name "unconnected-(D17-K-Pad1)") (class "Default")
      (node (ref "D17") (pin "1") (pinfunction "K_1") (pintype "passive"))
    )
    (net (code "117") (name "unconnected-(D18-K-Pad1)") (class "Default")
      (node (ref "D18") (pin "1") (pinfunction "K_1") (pintype "passive"))
    )
    (net (code "118") (name "unconnected-(J2-Pad2)") (class "Default")
      (node (ref "J2") (pin "2") (pinfunction "2_2") (pintype "passive"))
    )
    (net (code "119") (name "unconnected-(J2-Pad5)") (class "Default")
      (node (ref "J2") (pin "5") (pinfunction "5_5") (pintype "passive"))
    )
    (net (code "120") (name "unconnected-(J2-Pad9)") (class "Default")
      (node (ref "J2") (pin "9") (pinfunction "9_9") (pintype "passive"))
    )
    (net (code "121") (name "unconnected-(J2-Pad13)") (class "Default")
      (node (ref "J2") (pin "13") (pinfunction "13_13") (pintype "passive"))
    )
    (net (code "122") (name "unconnected-(J2-Pad17)") (class "Default")
      (node (ref "J2") (pin "17") (pinfunction "17_17") (pintype "passive"))
    )
    (net (code "123") (name "unconnected-(J2-Pad19)") (class "Default")
      (node (ref "J2") (pin "19") (pinfunction "19_19") (pintype "passive"))
    )
    (net (code "124") (name "unconnected-(J3-Pad2)") (class "Default")
      (node (ref "J3") (pin "2") (pinfunction "2_2") (pintype "passive"))
    )
    (net (code "125") (name "unconnected-(J3-Pad5)") (class "Default")
      (node (ref "J3") (pin "5") (pinfunction "5_5") (pintype "passive"))
    )
    (net (code "126") (name "unconnected-(J3-Pad7)") (class "Default")
      (node (ref "J3") (pin "7") (pinfunction "7_7") (pintype "passive"))
    )
    (net (code "127") (name "unconnected-(J3-Pad9)") (class "Default")
      (node (ref "J3") (pin "9") (pinfunction "9_9") (pintype "passive"))
    )
    (net (code "128") (name "unconnected-(J3-Pad12)") (class "Default")
      (node (ref "J3") (pin "12") (pinfunction "12_12") (pintype "passive"))
    )
    (net (code "129") (name "unconnected-(J3-Pad13)") (class "Default")
      (node (ref "J3") (pin "13") (pinfunction "13_13") (pintype "passive"))
    )
    (net (code "130") (name "unconnected-(J3-Pad17)") (class "Default")
      (node (ref "J3") (pin "17") (pinfunction "17_17") (pintype "passive"))
    )
    (net (code "131") (name "unconnected-(J3-Pad19)") (class "Default")
      (node (ref "J3") (pin "19") (pinfunction "19_19") (pintype "passive"))
    )
    (net (code "132") (name "unconnected-(J4-Pad2)") (class "Default")
      (node (ref "J4") (pin "2") (pinfunction "2_2") (pintype "passive"))
    )
    (net (code "133") (name "unconnected-(J4-Pad6)") (class "Default")
      (node (ref "J4") (pin "6") (pinfunction "6_6") (pintype "passive"))
    )
    (net (code "134") (name "unconnected-(J4-Pad8)") (class "Default")
      (node (ref "J4") (pin "8") (pinfunction "8_8") (pintype "passive"))
    )
    (net (code "135") (name "unconnected-(J4-Pad10)") (class "Default")
      (node (ref "J4") (pin "10") (pinfunction "10_10") (pintype "passive"))
    )
    (net (code "136") (name "unconnected-(J4-Pad17)") (class "Default")
      (node (ref "J4") (pin "17") (pinfunction "17_17") (pintype "passive"))
    )
    (net (code "137") (name "unconnected-(J5-Pad2)") (class "Default")
      (node (ref "J5") (pin "2") (pinfunction "2_2") (pintype "passive"))
    )
    (net (code "138") (name "unconnected-(J5-Pad4)") (class "Default")
      (node (ref "J5") (pin "4") (pinfunction "4_4") (pintype "passive"))
    )
    (net (code "139") (name "unconnected-(J5-Pad6)") (class "Default")
      (node (ref "J5") (pin "6") (pinfunction "6_6") (pintype "passive"))
    )
    (net (code "140") (name "unconnected-(J5-Pad8)") (class "Default")
      (node (ref "J5") (pin "8") (pinfunction "8_8") (pintype "passive"))
    )
    (net (code "141") (name "unconnected-(J5-Pad10)") (class "Default")
      (node (ref "J5") (pin "10") (pinfunction "10_10") (pintype "passive"))
    )
    (net (code "142") (name "unconnected-(J5-Pad12)") (class "Default")
      (node (ref "J5") (pin "12") (pinfunction "12_12") (pintype "passive"))
    )
    (net (code "143") (name "unconnected-(J5-Pad14)") (class "Default")
      (node (ref "J5") (pin "14") (pinfunction "14_14") (pintype "passive"))
    )
    (net (code "144") (name "unconnected-(J5-Pad16)") (class "Default")
      (node (ref "J5") (pin "16") (pinfunction "16_16") (pintype "passive"))
    )
    (net (code "145") (name "unconnected-(J5-Pad17)") (class "Default")
      (node (ref "J5") (pin "17") (pinfunction "17_17") (pintype "passive"))
    )
    (net (code "146") (name "unconnected-(J5-Pad18)") (class "Default")
      (node (ref "J5") (pin "18") (pinfunction "18_18") (pintype "passive"))
    )
    (net (code "147") (name "unconnected-(J5-Pad19)") (class "Default")
      (node (ref "J5") (pin "19") (pinfunction "19_19") (pintype "passive"))
    )
    (net (code "148") (name "unconnected-(J5-Pad20)") (class "Default")
      (node (ref "J5") (pin "20") (pinfunction "20_20") (pintype "passive"))
    )
    (net (code "149") (name "unconnected-(P9-Pad1)") (class "Default")
      (node (ref "P9") (pin "1") (pinfunction "1_1") (pintype "passive"))
    )
    (net (code "150") (name "unconnected-(R13-Pad1)") (class "Default")
      (node (ref "R13") (pin "1") (pinfunction "1_1") (pintype "passive"))
    )
    (net (code "151") (name "unconnected-(R13-Pad2)") (class "Default")
      (node (ref "R13") (pin "2") (pinfunction "2_2") (pintype "passive"))
    )
  )
)
